# Ref_3V0_LM4132AMF.net
KiCad netlist of a schematic drawn in Altium Designer
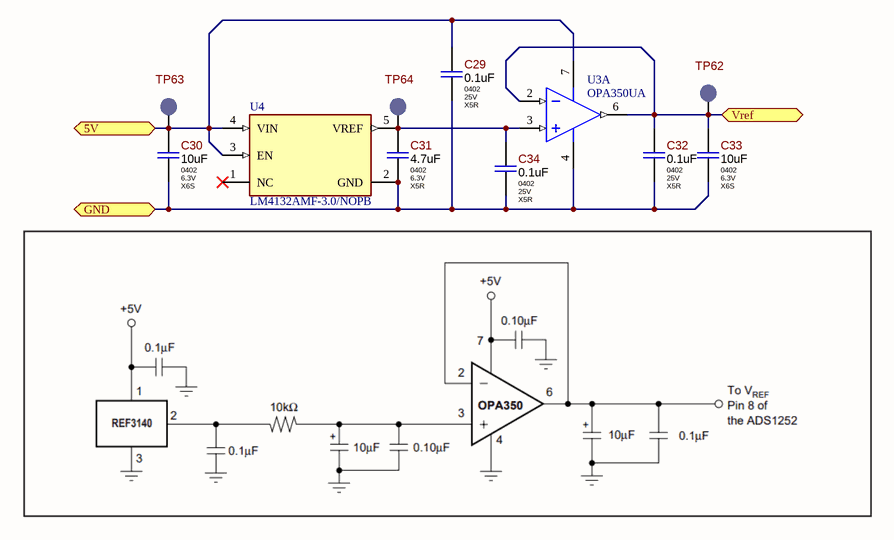
[diagram p0: Ref_3V0_LM4132AMF.SchDoc]

(export (version "E")
  (design (tool "Eeschema 10.0.6"))
  (components
    (comp (ref "C29")
      (value "0.1uF")
      (footprint "C_CERAMIC_0402_MED")
      (description "100nF 25V X5R ±10% 0402 Ceramic Capacitor RoHS")
      (fields
        (field (name "PACKAGE") "0402")
        (field (name "VOLTAGE") "25V")
        (field (name "DIELECTRIC TYPE") "X5R")
        (field (name "PART NUMBER") "CL05A104KA5NNNC")
        (field (name "MANUFACTURER") "Samsung Electro-Mechanics")
      )
      (libsource (lib "EL.XXX.T01") (part "Capacitor-NonPolar"))
    )
    (comp (ref "C30")
      (value "10uF")
      (footprint "C_CERAMIC_0402_MED")
      (description "10uF 6.3V X6S ±20% 0402 Ceramic Capacitor RoHS")
      (fields
        (field (name "PACKAGE") "0402")
        (field (name "VOLTAGE") "6.3V")
        (field (name "DIELECTRIC TYPE") "X6S")
        (field (name "PART NUMBER") "GRM155C80J106ME11D")
        (field (name "MANUFACTURER") "Murata Electronics")
      )
      (libsource (lib "EL.XXX.T01") (part "Capacitor-NonPolar"))
    )
    (comp (ref "C31")
      (value "4.7uF")
      (footprint "C_CERAMIC_0402_MED")
      (description "4.7uF 6.3V X5R ±20% 0402 Ceramic Capacitor RoHS")
      (fields
        (field (name "PACKAGE") "0402")
        (field (name "VOLTAGE") "6.3V")
        (field (name "DIELECTRIC TYPE") "X5R")
        (field (name "PART NUMBER") "GRM155R60J475ME47")
        (field (name "MANUFACTURER") "Murata Electronics")
      )
      (libsource (lib "EL.XXX.T01") (part "Capacitor-NonPolar"))
    )
    (comp (ref "C32")
      (value "0.1uF")
      (footprint "C_CERAMIC_0402_MED")
      (description "100nF 25V X5R ±10% 0402 Ceramic Capacitor RoHS")
      (fields
        (field (name "PACKAGE") "0402")
        (field (name "VOLTAGE") "25V")
        (field (name "DIELECTRIC TYPE") "X5R")
        (field (name "PART NUMBER") "CL05A104KA5NNNC")
        (field (name "MANUFACTURER") "Samsung Electro-Mechanics")
      )
      (libsource (lib "EL.XXX.T01") (part "Capacitor-NonPolar"))
    )
    (comp (ref "C33")
      (value "10uF")
      (footprint "C_CERAMIC_0402_MED")
      (description "10uF 6.3V X6S ±20% 0402 Ceramic Capacitor RoHS")
      (fields
        (field (name "PACKAGE") "0402")
        (field (name "VOLTAGE") "6.3V")
        (field (name "DIELECTRIC TYPE") "X6S")
        (field (name "PART NUMBER") "GRM155C80J106ME11D")
        (field (name "MANUFACTURER") "Murata Electronics")
      )
      (libsource (lib "EL.XXX.T01") (part "Capacitor-NonPolar"))
    )
    (comp (ref "C34")
      (value "0.1uF")
      (footprint "C_CERAMIC_0402_MED")
      (description "100nF 25V X5R ±10% 0402 Ceramic Capacitor RoHS")
      (fields
        (field (name "PACKAGE") "0402")
        (field (name "VOLTAGE") "25V")
        (field (name "DIELECTRIC TYPE") "X5R")
        (field (name "PART NUMBER") "CL05A104KA5NNNC")
        (field (name "MANUFACTURER") "Samsung Electro-Mechanics")
      )
      (libsource (lib "EL.XXX.T01") (part "Capacitor-NonPolar"))
    )
    (comp (ref "TP62")
      (value "LED_LINK")
      (footprint "TP_SMD_2mm")
      (description "Test Point SMD Pad 1.0mm/1.5mm/2mm")
      (fields (field (name "PART NUMBER") "TP-PAD-SMD"))
      (libsource (lib "EL.XXX.T01") (part "Test-Point-SMD-1"))
    )
    (comp (ref "TP63")
      (value "LED_LINK")
      (footprint "TP_SMD_2mm")
      (description "Test Point SMD Pad 1.0mm/1.5mm/2mm")
      (fields (field (name "PART NUMBER") "TP-PAD-SMD"))
      (libsource (lib "EL.XXX.T01") (part "Test-Point-SMD-1"))
    )
    (comp (ref "TP64")
      (value "LED_LINK")
      (footprint "TP_SMD_2mm")
      (description "Test Point SMD Pad 1.0mm/1.5mm/2mm")
      (fields (field (name "PART NUMBER") "TP-PAD-SMD"))
      (libsource (lib "EL.XXX.T01") (part "Test-Point-SMD-1"))
    )
    (comp (ref "U3")
      (value "OPA350UA")
      (footprint "D0008A_M")
      (fields (field (name "MANUFACTURER") "Texas Instruments"))
      (libsource (lib "EL.XXX.T01") (part "TI-OPA-8_1"))
    )
    (comp (ref "U4")
      (value "LM4132AMF-3.0/NOPB")
      (footprint "SOT-23-5")
      (description "IC VREF SERIES 0.05% SOT23-5")
      (fields (field (name "TOLERANCE") "0.05%"))
      (libsource (lib "EL.XXX.T01") (part "LM4132AMF-3.0/NOPB"))
    )
  )
  (nets
    (net (code "1") (name "/5V") (class "Default")
      (node (ref "C29") (pin "1") (pinfunction "1_1") (pintype "passive"))
      (node (ref "C30") (pin "1") (pinfunction "1_1") (pintype "passive"))
      (node (ref "TP63") (pin "1") (pintype "passive"))
      (node (ref "U3") (pin "7") (pinfunction "V+_7") (pintype "power_in"))
      (node (ref "U4") (pin "3") (pinfunction "EN_3") (pintype "input"))
      (node (ref "U4") (pin "4") (pinfunction "VIN_4") (pintype "input"))
    )
    (net (code "2") (name "/GND") (class "Default")
      (node (ref "C29") (pin "2") (pinfunction "2_2") (pintype "passive"))
      (node (ref "C30") (pin "2") (pinfunction "2_2") (pintype "passive"))
      (node (ref "C31") (pin "2") (pinfunction "2_2") (pintype "passive"))
      (node (ref "C32") (pin "2") (pinfunction "2_2") (pintype "passive"))
      (node (ref "C33") (pin "2") (pinfunction "2_2") (pintype "passive"))
      (node (ref "C34") (pin "2") (pinfunction "2_2") (pintype "passive"))
      (node (ref "U3") (pin "4") (pinfunction "V-_4") (pintype "power_in"))
      (node (ref "U4") (pin "2") (pinfunction "GND_2") (pintype "power_in"))
    )
    (net (code "3") (name "/Vref") (class "Default")
      (node (ref "C32") (pin "1") (pinfunction "1_1") (pintype "passive"))
      (node (ref "C33") (pin "1") (pinfunction "1_1") (pintype "passive"))
      (node (ref "TP62") (pin "1") (pintype "passive"))
      (node (ref "U3") (pin "2") (pinfunction "IN-_2") (pintype "input"))
      (node (ref "U3") (pin "6") (pinfunction "OUT_6") (pintype "output"))
    )
    (net (code "4") (name "Net-(U3A-IN+)") (class "Default")
      (node (ref "C31") (pin "1") (pinfunction "1_1") (pintype "passive"))
      (node (ref "C34") (pin "1") (pinfunction "1_1") (pintype "passive"))
      (node (ref "TP64") (pin "1") (pintype "passive"))
      (node (ref "U3") (pin "3") (pinfunction "IN+_3") (pintype "input"))
      (node (ref "U4") (pin "5") (pinfunction "VREF_5") (pintype "output"))
    )
    (net (code "5") (name "unconnected-(U4-NC-Pad1)") (class "Default")
      (node (ref "U4") (pin "1") (pinfunction "NC_1") (pintype "passive+no_connect"))
    )
  )
)
